# XMICRO-BREAKOUT-CARD.net
KiCad netlist of a schematic drawn in EAGLE
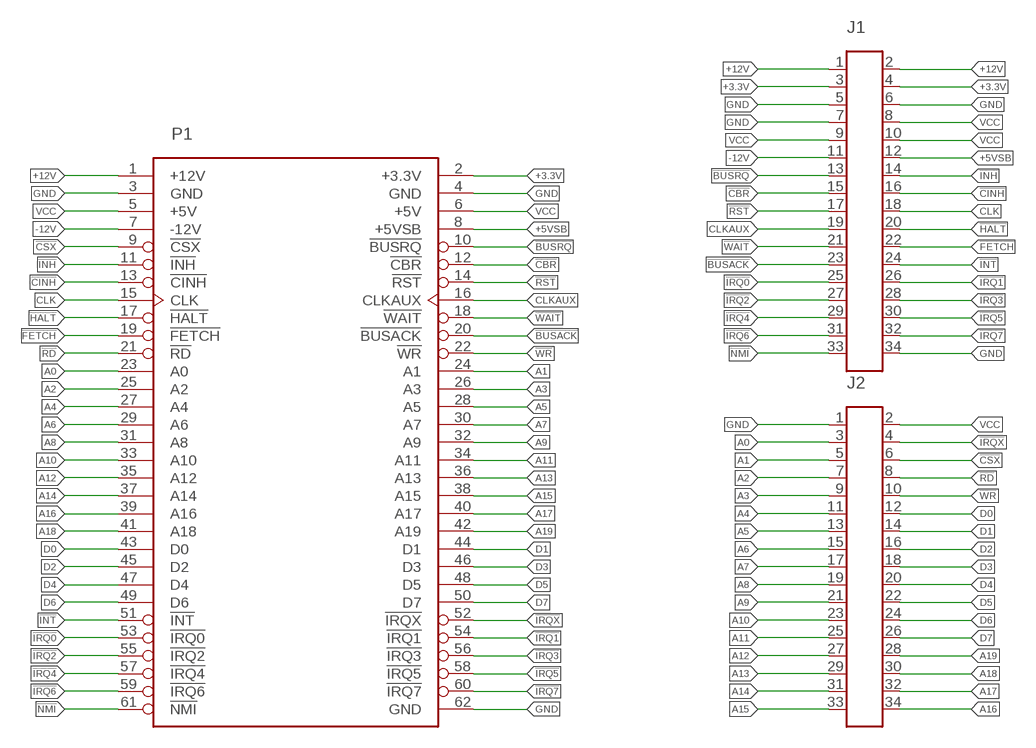
[diagram p0: schematic, sheet 1]

(export (version "E")
  (design (tool "Eeschema 10.0.6"))
  (components
    (comp (ref "J1")
      (value "HDR-17X2")
      (footprint "eagle-import:HDR-17X2S")
      (libsource (lib "eagle-import") (part "HDR-17X2"))
    )
    (comp (ref "J2")
      (value "HDR-17X2")
      (footprint "eagle-import:HDR-17X2S")
      (libsource (lib "eagle-import") (part "HDR-17X2"))
    )
    (comp (ref "P1")
      (value "XMICRO-BUS-PHYSICAL-EDGE62M")
      (footprint "eagle-import:EDGE62M")
      (libsource (lib "eagle-import") (part "XMICRO-BUS-PHYSICAL-EDGE62M"))
    )
  )
  (nets
    (net (code "1") (name "+3.3V") (class "Default")
      (node (ref "J1") (pin "3") (pinfunction "3_3") (pintype "bidirectional"))
      (node (ref "J1") (pin "4") (pinfunction "4_4") (pintype "bidirectional"))
      (node (ref "P1") (pin "2") (pinfunction "+3.3V_2") (pintype "bidirectional"))
    )
    (net (code "2") (name "+5VSB") (class "Default")
      (node (ref "J1") (pin "12") (pinfunction "12_12") (pintype "bidirectional"))
      (node (ref "P1") (pin "8") (pinfunction "+5VSB_8") (pintype "bidirectional"))
    )
    (net (code "3") (name "+12V") (class "Default")
      (node (ref "J1") (pin "1") (pinfunction "1_1") (pintype "bidirectional"))
      (node (ref "J1") (pin "2") (pinfunction "2_2") (pintype "bidirectional"))
      (node (ref "P1") (pin "1") (pinfunction "+12V_1") (pintype "bidirectional"))
    )
    (net (code "4") (name "-12V") (class "Default")
      (node (ref "J1") (pin "11") (pinfunction "11_11") (pintype "bidirectional"))
      (node (ref "P1") (pin "7") (pinfunction "-12V_7") (pintype "bidirectional"))
    )
    (net (code "5") (name "/~{BUSACK}") (class "Default")
      (node (ref "J1") (pin "23") (pinfunction "23_23") (pintype "bidirectional"))
      (node (ref "P1") (pin "20") (pinfunction "~{BUSACK}_20") (pintype "bidirectional"))
    )
    (net (code "6") (name "/~{BUSRQ}") (class "Default")
      (node (ref "J1") (pin "13") (pinfunction "13_13") (pintype "bidirectional"))
      (node (ref "P1") (pin "10") (pinfunction "~{BUSRQ}_10") (pintype "bidirectional"))
    )
    (net (code "7") (name "/~{CBR}") (class "Default")
      (node (ref "J1") (pin "15") (pinfunction "15_15") (pintype "bidirectional"))
      (node (ref "P1") (pin "12") (pinfunction "~{CBR}_12") (pintype "bidirectional"))
    )
    (net (code "8") (name "/~{CINH}") (class "Default")
      (node (ref "J1") (pin "16") (pinfunction "16_16") (pintype "bidirectional"))
      (node (ref "P1") (pin "13") (pinfunction "~{CINH}_13") (pintype "bidirectional"))
    )
    (net (code "9") (name "/~{CSX}") (class "Default")
      (node (ref "J2") (pin "6") (pinfunction "6_6") (pintype "bidirectional"))
      (node (ref "P1") (pin "9") (pinfunction "~{CSX}_9") (pintype "bidirectional"))
    )
    (net (code "10") (name "/~{FETCH}") (class "Default")
      (node (ref "J1") (pin "22") (pinfunction "22_22") (pintype "bidirectional"))
      (node (ref "P1") (pin "19") (pinfunction "~{FETCH}_19") (pintype "bidirectional"))
    )
    (net (code "11") (name "/~{HALT}") (class "Default")
      (node (ref "J1") (pin "20") (pinfunction "20_20") (pintype "bidirectional"))
      (node (ref "P1") (pin "17") (pinfunction "~{HALT}_17") (pintype "bidirectional"))
    )
    (net (code "12") (name "/~{INH}") (class "Default")
      (node (ref "J1") (pin "14") (pinfunction "14_14") (pintype "bidirectional"))
      (node (ref "P1") (pin "11") (pinfunction "~{INH}_11") (pintype "bidirectional"))
    )
    (net (code "13") (name "/~{INT}") (class "Default")
      (node (ref "J1") (pin "24") (pinfunction "24_24") (pintype "bidirectional"))
      (node (ref "P1") (pin "51") (pinfunction "~{INT}_51") (pintype "bidirectional"))
    )
    (net (code "14") (name "/~{IRQ0}") (class "Default")
      (node (ref "J1") (pin "25") (pinfunction "25_25") (pintype "bidirectional"))
      (node (ref "P1") (pin "53") (pinfunction "~{IRQ0}_53") (pintype "bidirectional"))
    )
    (net (code "15") (name "/~{IRQ1}") (class "Default")
      (node (ref "J1") (pin "26") (pinfunction "26_26") (pintype "bidirectional"))
      (node (ref "P1") (pin "54") (pinfunction "~{IRQ1}_54") (pintype "bidirectional"))
    )
    (net (code "16") (name "/~{IRQ2}") (class "Default")
      (node (ref "J1") (pin "27") (pinfunction "27_27") (pintype "bidirectional"))
      (node (ref "P1") (pin "55") (pinfunction "~{IRQ2}_55") (pintype "bidirectional"))
    )
    (net (code "17") (name "/~{IRQ3}") (class "Default")
      (node (ref "J1") (pin "28") (pinfunction "28_28") (pintype "bidirectional"))
      (node (ref "P1") (pin "56") (pinfunction "~{IRQ3}_56") (pintype "bidirectional"))
    )
    (net (code "18") (name "/~{IRQ4}") (class "Default")
      (node (ref "J1") (pin "29") (pinfunction "29_29") (pintype "bidirectional"))
      (node (ref "P1") (pin "57") (pinfunction "~{IRQ4}_57") (pintype "bidirectional"))
    )
    (net (code "19") (name "/~{IRQ5}") (class "Default")
      (node (ref "J1") (pin "30") (pinfunction "30_30") (pintype "bidirectional"))
      (node (ref "P1") (pin "58") (pinfunction "~{IRQ5}_58") (pintype "bidirectional"))
    )
    (net (code "20") (name "/~{IRQ6}") (class "Default")
      (node (ref "J1") (pin "31") (pinfunction "31_31") (pintype "bidirectional"))
      (node (ref "P1") (pin "59") (pinfunction "~{IRQ6}_59") (pintype "bidirectional"))
    )
    (net (code "21") (name "/~{IRQ7}") (class "Default")
      (node (ref "J1") (pin "32") (pinfunction "32_32") (pintype "bidirectional"))
      (node (ref "P1") (pin "60") (pinfunction "~{IRQ7}_60") (pintype "bidirectional"))
    )
    (net (code "22") (name "/~{IRQX}") (class "Default")
      (node (ref "J2") (pin "4") (pinfunction "4_4") (pintype "bidirectional"))
      (node (ref "P1") (pin "52") (pinfunction "~{IRQX}_52") (pintype "bidirectional"))
    )
    (net (code "23") (name "/~{NMI}") (class "Default")
      (node (ref "J1") (pin "33") (pinfunction "33_33") (pintype "bidirectional"))
      (node (ref "P1") (pin "61") (pinfunction "~{NMI}_61") (pintype "bidirectional"))
    )
    (net (code "24") (name "/~{RD}") (class "Default")
      (node (ref "J2") (pin "8") (pinfunction "8_8") (pintype "bidirectional"))
      (node (ref "P1") (pin "21") (pinfunction "~{RD}_21") (pintype "bidirectional"))
    )
    (net (code "25") (name "/~{RST}") (class "Default")
      (node (ref "J1") (pin "17") (pinfunction "17_17") (pintype "bidirectional"))
      (node (ref "P1") (pin "14") (pinfunction "~{RST}_14") (pintype "bidirectional"))
    )
    (net (code "26") (name "/~{WAIT}") (class "Default")
      (node (ref "J1") (pin "21") (pinfunction "21_21") (pintype "bidirectional"))
      (node (ref "P1") (pin "18") (pinfunction "~{WAIT}_18") (pintype "bidirectional"))
    )
    (net (code "27") (name "/~{WR}") (class "Default")
      (node (ref "J2") (pin "10") (pinfunction "10_10") (pintype "bidirectional"))
      (node (ref "P1") (pin "22") (pinfunction "~{WR}_22") (pintype "bidirectional"))
    )
    (net (code "28") (name "A0") (class "Default")
      (node (ref "J2") (pin "3") (pinfunction "3_3") (pintype "bidirectional"))
      (node (ref "P1") (pin "23") (pinfunction "A0_23") (pintype "bidirectional"))
    )
    (net (code "29") (name "A1") (class "Default")
      (node (ref "J2") (pin "5") (pinfunction "5_5") (pintype "bidirectional"))
      (node (ref "P1") (pin "24") (pinfunction "A1_24") (pintype "bidirectional"))
    )
    (net (code "30") (name "A2") (class "Default")
      (node (ref "J2") (pin "7") (pinfunction "7_7") (pintype "bidirectional"))
      (node (ref "P1") (pin "25") (pinfunction "A2_25") (pintype "bidirectional"))
    )
    (net (code "31") (name "A3") (class "Default")
      (node (ref "J2") (pin "9") (pinfunction "9_9") (pintype "bidirectional"))
      (node (ref "P1") (pin "26") (pinfunction "A3_26") (pintype "bidirectional"))
    )
    (net (code "32") (name "A4") (class "Default")
      (node (ref "J2") (pin "11") (pinfunction "11_11") (pintype "bidirectional"))
      (node (ref "P1") (pin "27") (pinfunction "A4_27") (pintype "bidirectional"))
    )
    (net (code "33") (name "A5") (class "Default")
      (node (ref "J2") (pin "13") (pinfunction "13_13") (pintype "bidirectional"))
      (node (ref "P1") (pin "28") (pinfunction "A5_28") (pintype "bidirectional"))
    )
    (net (code "34") (name "A6") (class "Default")
      (node (ref "J2") (pin "15") (pinfunction "15_15") (pintype "bidirectional"))
      (node (ref "P1") (pin "29") (pinfunction "A6_29") (pintype "bidirectional"))
    )
    (net (code "35") (name "A7") (class "Default")
      (node (ref "J2") (pin "17") (pinfunction "17_17") (pintype "bidirectional"))
      (node (ref "P1") (pin "30") (pinfunction "A7_30") (pintype "bidirectional"))
    )
    (net (code "36") (name "A8") (class "Default")
      (node (ref "J2") (pin "19") (pinfunction "19_19") (pintype "bidirectional"))
      (node (ref "P1") (pin "31") (pinfunction "A8_31") (pintype "bidirectional"))
    )
    (net (code "37") (name "A9") (class "Default")
      (node (ref "J2") (pin "21") (pinfunction "21_21") (pintype "bidirectional"))
      (node (ref "P1") (pin "32") (pinfunction "A9_32") (pintype "bidirectional"))
    )
    (net (code "38") (name "A10") (class "Default")
      (node (ref "J2") (pin "23") (pinfunction "23_23") (pintype "bidirectional"))
      (node (ref "P1") (pin "33") (pinfunction "A10_33") (pintype "bidirectional"))
    )
    (net (code "39") (name "A11") (class "Default")
      (node (ref "J2") (pin "25") (pinfunction "25_25") (pintype "bidirectional"))
      (node (ref "P1") (pin "34") (pinfunction "A11_34") (pintype "bidirectional"))
    )
    (net (code "40") (name "A12") (class "Default")
      (node (ref "J2") (pin "27") (pinfunction "27_27") (pintype "bidirectional"))
      (node (ref "P1") (pin "35") (pinfunction "A12_35") (pintype "bidirectional"))
    )
    (net (code "41") (name "A13") (class "Default")
      (node (ref "J2") (pin "29") (pinfunction "29_29") (pintype "bidirectional"))
      (node (ref "P1") (pin "36") (pinfunction "A13_36") (pintype "bidirectional"))
    )
    (net (code "42") (name "A14") (class "Default")
      (node (ref "J2") (pin "31") (pinfunction "31_31") (pintype "bidirectional"))
      (node (ref "P1") (pin "37") (pinfunction "A14_37") (pintype "bidirectional"))
    )
    (net (code "43") (name "A15") (class "Default")
      (node (ref "J2") (pin "33") (pinfunction "33_33") (pintype "bidirectional"))
      (node (ref "P1") (pin "38") (pinfunction "A15_38") (pintype "bidirectional"))
    )
    (net (code "44") (name "A16") (class "Default")
      (node (ref "J2") (pin "34") (pinfunction "34_34") (pintype "bidirectional"))
      (node (ref "P1") (pin "39") (pinfunction "A16_39") (pintype "bidirectional"))
    )
    (net (code "45") (name "A17") (class "Default")
      (node (ref "J2") (pin "32") (pinfunction "32_32") (pintype "bidirectional"))
      (node (ref "P1") (pin "40") (pinfunction "A17_40") (pintype "bidirectional"))
    )
    (net (code "46") (name "A18") (class "Default")
      (node (ref "J2") (pin "30") (pinfunction "30_30") (pintype "bidirectional"))
      (node (ref "P1") (pin "41") (pinfunction "A18_41") (pintype "bidirectional"))
    )
    (net (code "47") (name "A19") (class "Default")
      (node (ref "J2") (pin "28") (pinfunction "28_28") (pintype "bidirectional"))
      (node (ref "P1") (pin "42") (pinfunction "A19_42") (pintype "bidirectional"))
    )
    (net (code "48") (name "CLK") (class "Default")
      (node (ref "J1") (pin "18") (pinfunction "18_18") (pintype "bidirectional"))
      (node (ref "P1") (pin "15") (pinfunction "CLK_15") (pintype "bidirectional"))
    )
    (net (code "49") (name "CLKAUX") (class "Default")
      (node (ref "J1") (pin "19") (pinfunction "19_19") (pintype "bidirectional"))
      (node (ref "P1") (pin "16") (pinfunction "CLKAUX_16") (pintype "bidirectional"))
    )
    (net (code "50") (name "D0") (class "Default")
      (node (ref "J2") (pin "12") (pinfunction "12_12") (pintype "bidirectional"))
      (node (ref "P1") (pin "43") (pinfunction "D0_43") (pintype "bidirectional"))
    )
    (net (code "51") (name "D1") (class "Default")
      (node (ref "J2") (pin "14") (pinfunction "14_14") (pintype "bidirectional"))
      (node (ref "P1") (pin "44") (pinfunction "D1_44") (pintype "bidirectional"))
    )
    (net (code "52") (name "D2") (class "Default")
      (node (ref "J2") (pin "16") (pinfunction "16_16") (pintype "bidirectional"))
      (node (ref "P1") (pin "45") (pinfunction "D2_45") (pintype "bidirectional"))
    )
    (net (code "53") (name "D3") (class "Default")
      (node (ref "J2") (pin "18") (pinfunction "18_18") (pintype "bidirectional"))
      (node (ref "P1") (pin "46") (pinfunction "D3_46") (pintype "bidirectional"))
    )
    (net (code "54") (name "D4") (class "Default")
      (node (ref "J2") (pin "20") (pinfunction "20_20") (pintype "bidirectional"))
      (node (ref "P1") (pin "47") (pinfunction "D4_47") (pintype "bidirectional"))
    )
    (net (code "55") (name "D5") (class "Default")
      (node (ref "J2") (pin "22") (pinfunction "22_22") (pintype "bidirectional"))
      (node (ref "P1") (pin "48") (pinfunction "D5_48") (pintype "bidirectional"))
    )
    (net (code "56") (name "D6") (class "Default")
      (node (ref "J2") (pin "24") (pinfunction "24_24") (pintype "bidirectional"))
      (node (ref "P1") (pin "49") (pinfunction "D6_49") (pintype "bidirectional"))
    )
    (net (code "57") (name "D7") (class "Default")
      (node (ref "J2") (pin "26") (pinfunction "26_26") (pintype "bidirectional"))
      (node (ref "P1") (pin "50") (pinfunction "D7_50") (pintype "bidirectional"))
    )
    (net (code "58") (name "GND") (class "Default")
      (node (ref "J1") (pin "34") (pinfunction "34_34") (pintype "bidirectional"))
      (node (ref "J1") (pin "5") (pinfunction "5_5") (pintype "bidirectional"))
      (node (ref "J1") (pin "6") (pinfunction "6_6") (pintype "bidirectional"))
      (node (ref "J1") (pin "7") (pinfunction "7_7") (pintype "bidirectional"))
      (node (ref "J2") (pin "1") (pinfunction "1_1") (pintype "bidirectional"))
      (node (ref "P1") (pin "3") (pinfunction "GND_3") (pintype "bidirectional"))
      (node (ref "P1") (pin "4") (pinfunction "GND_4") (pintype "bidirectional"))
      (node (ref "P1") (pin "62") (pinfunction "GND_62") (pintype "bidirectional"))
    )
    (net (code "59") (name "VCC") (class "Default")
      (node (ref "J1") (pin "10") (pinfunction "10_10") (pintype "bidirectional"))
      (node (ref "J1") (pin "8") (pinfunction "8_8") (pintype "bidirectional"))
      (node (ref "J1") (pin "9") (pinfunction "9_9") (pintype "bidirectional"))
      (node (ref "J2") (pin "2") (pinfunction "2_2") (pintype "bidirectional"))
      (node (ref "P1") (pin "5") (pinfunction "+5V_5") (pintype "bidirectional"))
      (node (ref "P1") (pin "6") (pinfunction "+5V_6") (pintype "bidirectional"))
    )
  )
)
